# Shield.net
KiCad netlist of a schematic drawn in EAGLE
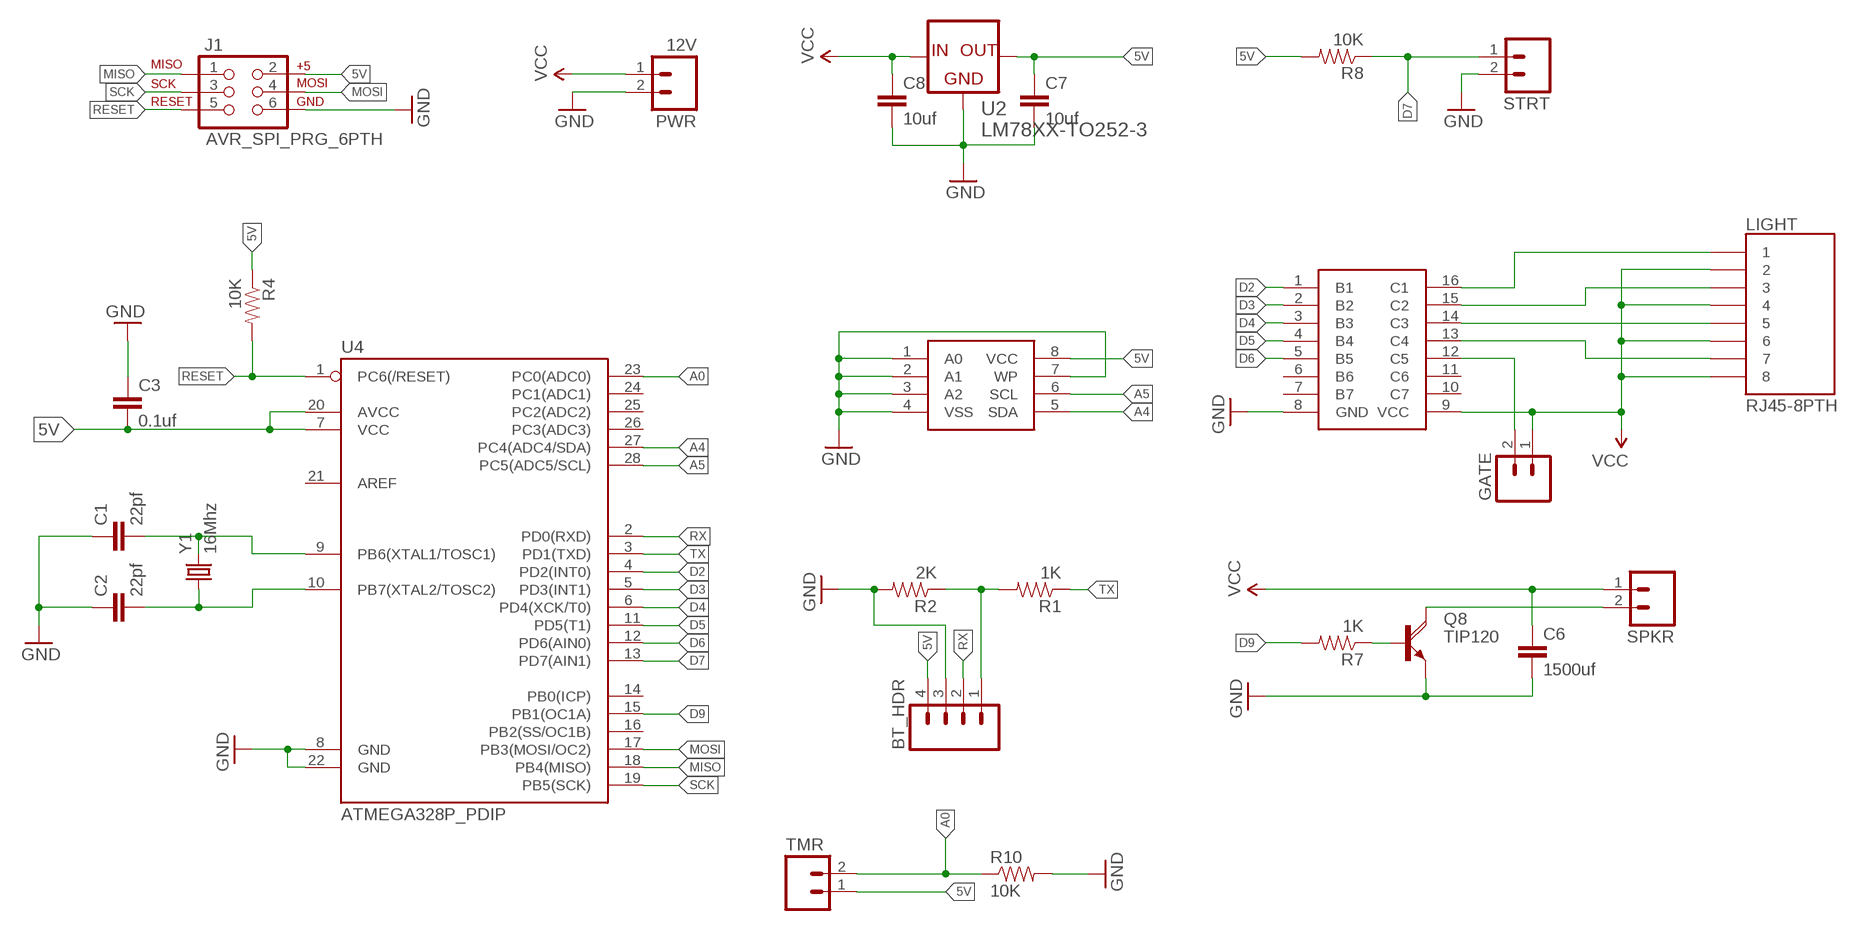
[diagram p0: schematic, sheet 1]

(export (version "E")
  (design (tool "Eeschema 10.0.6"))
  (components
    (comp (ref "BT_HDR")
      (value "M04PTH")
      (footprint "eagle-import:1X04")
      (libsource (lib "eagle-import") (part "M04PTH"))
    )
    (comp (ref "C1")
      (value "22pf")
      (footprint "eagle-import:1206")
      (libsource (lib "eagle-import") (part "CAP1206"))
    )
    (comp (ref "C2")
      (value "22pf")
      (footprint "eagle-import:1206")
      (libsource (lib "eagle-import") (part "CAP1206"))
    )
    (comp (ref "C3")
      (value "0.1uf")
      (footprint "eagle-import:1206")
      (libsource (lib "eagle-import") (part "CAP1206"))
    )
    (comp (ref "C6")
      (value "1500uf")
      (footprint "eagle-import:CAP-PTH-5MM")
      (libsource (lib "eagle-import") (part "CAPPTH1"))
    )
    (comp (ref "C7")
      (value "10uf")
      (footprint "eagle-import:CAP-PTH-SMALL")
      (libsource (lib "eagle-import") (part "CAPPTH"))
    )
    (comp (ref "C8")
      (value "10uf")
      (footprint "eagle-import:CAP-PTH-SMALL")
      (libsource (lib "eagle-import") (part "CAPPTH"))
    )
    (comp (ref "GATE")
      (value "M023.5MM")
      (footprint "eagle-import:SCREWTERMINAL-3.5MM-2")
      (libsource (lib "eagle-import") (part "M023.5MM"))
    )
    (comp (ref "J1")
      (value "AVR_SPI_PRG_6PTH")
      (footprint "eagle-import:2X3")
      (libsource (lib "eagle-import") (part "AVR_SPI_PRG_6PTH"))
    )
    (comp (ref "LIGHT")
      (value "RJ45-8PTH")
      (footprint "eagle-import:RJ45-8")
      (libsource (lib "eagle-import") (part "RJ45-8PTH"))
    )
    (comp (ref "PWR")
      (value "12V")
      (footprint "eagle-import:SCREWTERMINAL-3.5MM-2")
      (libsource (lib "eagle-import") (part "M023.5MM"))
    )
    (comp (ref "Q8")
      (value "TIP120")
      (footprint "eagle-import:TO220V")
      (libsource (lib "eagle-import") (part "TIP120"))
    )
    (comp (ref "R1")
      (value "1K")
      (footprint "eagle-import:1206")
      (libsource (lib "eagle-import") (part "RESISTOR1206"))
    )
    (comp (ref "R2")
      (value "2K")
      (footprint "eagle-import:1206")
      (libsource (lib "eagle-import") (part "RESISTOR1206"))
    )
    (comp (ref "R4")
      (value "10K")
      (footprint "eagle-import:1206")
      (libsource (lib "eagle-import") (part "RESISTOR1206"))
    )
    (comp (ref "R7")
      (value "1K")
      (footprint "eagle-import:1206")
      (libsource (lib "eagle-import") (part "RESISTOR1206"))
    )
    (comp (ref "R8")
      (value "10K")
      (footprint "eagle-import:1206")
      (libsource (lib "eagle-import") (part "RESISTOR1206"))
    )
    (comp (ref "R10")
      (value "10K")
      (footprint "eagle-import:1206")
      (libsource (lib "eagle-import") (part "RESISTOR1206"))
    )
    (comp (ref "SPKR")
      (value "M023.5MM")
      (footprint "eagle-import:SCREWTERMINAL-3.5MM-2")
      (libsource (lib "eagle-import") (part "M023.5MM"))
    )
    (comp (ref "STRT")
      (value "M023.5MM")
      (footprint "eagle-import:SCREWTERMINAL-3.5MM-2")
      (libsource (lib "eagle-import") (part "M023.5MM"))
    )
    (comp (ref "TMR")
      (value "M023.5MM")
      (footprint "eagle-import:SCREWTERMINAL-3.5MM-2")
      (libsource (lib "eagle-import") (part "M023.5MM"))
    )
    (comp (ref "U$1")
      (value "MC1413D")
      (footprint "eagle-import:SO016")
      (libsource (lib "eagle-import") (part "MC1413D"))
    )
    (comp (ref "U$2")
      (value "24AAXXX")
      (footprint "eagle-import:SOIC-8-EIAJ")
      (libsource (lib "eagle-import") (part "24AAXXX"))
    )
    (comp (ref "U2")
      (value "LM78XX-TO252-3")
      (footprint "eagle-import:TO252-3")
      (fields (field (name "MPN") "UA78M33CKVURG3"))
      (libsource (lib "eagle-import") (part "LM78XX-TO252-3"))
    )
    (comp (ref "U4")
      (value "ATMEGA328P_PDIP")
      (footprint "eagle-import:DIL28-3")
      (libsource (lib "eagle-import") (part "ATMEGA328P_PDIP"))
    )
    (comp (ref "Y1")
      (value "16Mhz")
      (footprint "eagle-import:HC49US")
      (libsource (lib "eagle-import") (part "CRYSTALHC49US"))
    )
  )
  (nets
    (net (code "1") (name "5V") (class "Default")
      (node (ref "BT_HDR") (pin "4") (pinfunction "4_4") (pintype "passive"))
      (node (ref "C3") (pin "2") (pinfunction "2_2") (pintype "passive"))
      (node (ref "C7") (pin "1") (pinfunction "1_1") (pintype "passive"))
      (node (ref "J1") (pin "2") (pinfunction "2_2") (pintype "passive"))
      (node (ref "R4") (pin "1") (pinfunction "1_1") (pintype "passive"))
      (node (ref "R8") (pin "2") (pinfunction "2_2") (pintype "passive"))
      (node (ref "TMR") (pin "1") (pinfunction "1_1") (pintype "passive"))
      (node (ref "U$2") (pin "8") (pinfunction "VCC_8") (pintype "bidirectional"))
      (node (ref "U2") (pin "3") (pinfunction "OUT_3") (pintype "output"))
      (node (ref "U4") (pin "20") (pinfunction "AVCC_20") (pintype "bidirectional"))
      (node (ref "U4") (pin "7") (pinfunction "VCC_7") (pintype "bidirectional"))
    )
    (net (code "2") (name "A0") (class "Default")
      (node (ref "R10") (pin "1") (pinfunction "1_1") (pintype "passive"))
      (node (ref "TMR") (pin "2") (pinfunction "2_2") (pintype "passive"))
      (node (ref "U4") (pin "23") (pinfunction "PC0(ADC0)_23") (pintype "bidirectional"))
    )
    (net (code "3") (name "A4") (class "Default")
      (node (ref "U$2") (pin "5") (pinfunction "SDA_5") (pintype "bidirectional"))
      (node (ref "U4") (pin "27") (pinfunction "PC4(ADC4/SDA)_27") (pintype "bidirectional"))
    )
    (net (code "4") (name "A5") (class "Default")
      (node (ref "U$2") (pin "6") (pinfunction "SCL_6") (pintype "bidirectional"))
      (node (ref "U4") (pin "28") (pinfunction "PC5(ADC5/SCL)_28") (pintype "bidirectional"))
    )
    (net (code "5") (name "D2") (class "Default")
      (node (ref "U$1") (pin "1") (pinfunction "B1_1") (pintype "bidirectional"))
      (node (ref "U4") (pin "4") (pinfunction "PD2(INT0)_4") (pintype "bidirectional"))
    )
    (net (code "6") (name "D3") (class "Default")
      (node (ref "U$1") (pin "2") (pinfunction "B2_2") (pintype "bidirectional"))
      (node (ref "U4") (pin "5") (pinfunction "PD3(INT1)_5") (pintype "bidirectional"))
    )
    (net (code "7") (name "D4") (class "Default")
      (node (ref "U$1") (pin "3") (pinfunction "B3_3") (pintype "bidirectional"))
      (node (ref "U4") (pin "6") (pinfunction "PD4(XCK/T0)_6") (pintype "bidirectional"))
    )
    (net (code "8") (name "D5") (class "Default")
      (node (ref "U$1") (pin "4") (pinfunction "B4_4") (pintype "bidirectional"))
      (node (ref "U4") (pin "11") (pinfunction "PD5(T1)_11") (pintype "bidirectional"))
    )
    (net (code "9") (name "D6") (class "Default")
      (node (ref "U$1") (pin "5") (pinfunction "B5_5") (pintype "bidirectional"))
      (node (ref "U4") (pin "12") (pinfunction "PD6(AIN0)_12") (pintype "bidirectional"))
    )
    (net (code "10") (name "D7") (class "Default")
      (node (ref "R8") (pin "1") (pinfunction "1_1") (pintype "passive"))
      (node (ref "STRT") (pin "1") (pinfunction "1_1") (pintype "passive"))
      (node (ref "U4") (pin "13") (pinfunction "PD7(AIN1)_13") (pintype "bidirectional"))
    )
    (net (code "11") (name "D9") (class "Default")
      (node (ref "R7") (pin "2") (pinfunction "2_2") (pintype "passive"))
      (node (ref "U4") (pin "15") (pinfunction "PB1(OC1A)_15") (pintype "bidirectional"))
    )
    (net (code "12") (name "GND") (class "Default")
      (node (ref "BT_HDR") (pin "3") (pinfunction "3_3") (pintype "passive"))
      (node (ref "C1") (pin "1") (pinfunction "1_1") (pintype "passive"))
      (node (ref "C2") (pin "1") (pinfunction "1_1") (pintype "passive"))
      (node (ref "C3") (pin "1") (pinfunction "1_1") (pintype "passive"))
      (node (ref "C6") (pin "2") (pinfunction "2_2") (pintype "passive"))
      (node (ref "C7") (pin "2") (pinfunction "2_2") (pintype "passive"))
      (node (ref "C8") (pin "2") (pinfunction "2_2") (pintype "passive"))
      (node (ref "J1") (pin "6") (pinfunction "6_6") (pintype "passive"))
      (node (ref "PWR") (pin "2") (pinfunction "2_2") (pintype "passive"))
      (node (ref "Q8") (pin "3") (pinfunction "E_3") (pintype "passive"))
      (node (ref "R10") (pin "2") (pinfunction "2_2") (pintype "passive"))
      (node (ref "R2") (pin "2") (pinfunction "2_2") (pintype "passive"))
      (node (ref "STRT") (pin "2") (pinfunction "2_2") (pintype "passive"))
      (node (ref "U$1") (pin "8") (pinfunction "GND_8") (pintype "bidirectional"))
      (node (ref "U$2") (pin "1") (pinfunction "A0_1") (pintype "bidirectional"))
      (node (ref "U$2") (pin "2") (pinfunction "A1_2") (pintype "bidirectional"))
      (node (ref "U$2") (pin "3") (pinfunction "A2_3") (pintype "bidirectional"))
      (node (ref "U$2") (pin "4") (pinfunction "VSS_4") (pintype "bidirectional"))
      (node (ref "U$2") (pin "7") (pinfunction "WP_7") (pintype "bidirectional"))
      (node (ref "U2") (pin "2") (pinfunction "COM_2") (pintype "passive"))
      (node (ref "U4") (pin "22") (pinfunction "GND_22") (pintype "bidirectional"))
      (node (ref "U4") (pin "8") (pinfunction "GND_8") (pintype "bidirectional"))
    )
    (net (code "13") (name "MISO") (class "Default")
      (node (ref "J1") (pin "1") (pinfunction "1_1") (pintype "passive"))
      (node (ref "U4") (pin "18") (pinfunction "PB4(MISO)_18") (pintype "bidirectional"))
    )
    (net (code "14") (name "MOSI") (class "Default")
      (node (ref "J1") (pin "4") (pinfunction "4_4") (pintype "passive"))
      (node (ref "U4") (pin "17") (pinfunction "PB3(MOSI/OC2)_17") (pintype "bidirectional"))
    )
    (net (code "15") (name "Net-(BT_HDR-Pad1)") (class "Default")
      (node (ref "BT_HDR") (pin "1") (pinfunction "1_1") (pintype "passive"))
      (node (ref "R1") (pin "2") (pinfunction "2_2") (pintype "passive"))
      (node (ref "R2") (pin "1") (pinfunction "1_1") (pintype "passive"))
    )
    (net (code "16") (name "Net-(Q8-B)") (class "Default")
      (node (ref "Q8") (pin "1") (pinfunction "B_1") (pintype "passive"))
      (node (ref "R7") (pin "1") (pinfunction "1_1") (pintype "passive"))
    )
    (net (code "17") (name "Net-(Q8-C)") (class "Default")
      (node (ref "Q8") (pin "2") (pinfunction "C_2") (pintype "passive"))
      (node (ref "SPKR") (pin "2") (pinfunction "2_2") (pintype "passive"))
    )
    (net (code "18") (name "Net-(U$1-C1)") (class "Default")
      (node (ref "LIGHT") (pin "1") (pinfunction "1_1") (pintype "bidirectional"))
      (node (ref "U$1") (pin "16") (pinfunction "C1_16") (pintype "bidirectional"))
    )
    (net (code "19") (name "Net-(U$1-C2)") (class "Default")
      (node (ref "LIGHT") (pin "3") (pinfunction "3_3") (pintype "bidirectional"))
      (node (ref "U$1") (pin "15") (pinfunction "C2_15") (pintype "bidirectional"))
    )
    (net (code "20") (name "Net-(U$1-C3)") (class "Default")
      (node (ref "LIGHT") (pin "5") (pinfunction "5_5") (pintype "bidirectional"))
      (node (ref "U$1") (pin "14") (pinfunction "C3_14") (pintype "bidirectional"))
    )
    (net (code "21") (name "Net-(U$1-C4)") (class "Default")
      (node (ref "LIGHT") (pin "7") (pinfunction "7_7") (pintype "bidirectional"))
      (node (ref "U$1") (pin "13") (pinfunction "C4_13") (pintype "bidirectional"))
    )
    (net (code "22") (name "Net-(U$1-C5)") (class "Default")
      (node (ref "GATE") (pin "2") (pinfunction "2_2") (pintype "passive"))
      (node (ref "U$1") (pin "12") (pinfunction "C5_12") (pintype "bidirectional"))
    )
    (net (code "23") (name "Net-(U4-PB6(XTAL1{slash}TOSC1))") (class "Default")
      (node (ref "C1") (pin "2") (pinfunction "2_2") (pintype "passive"))
      (node (ref "U4") (pin "9") (pinfunction "PB6(XTAL1/TOSC1)_9") (pintype "bidirectional"))
      (node (ref "Y1") (pin "2") (pinfunction "2_2") (pintype "passive"))
    )
    (net (code "24") (name "Net-(U4-PB7(XTAL2{slash}TOSC2))") (class "Default")
      (node (ref "C2") (pin "2") (pinfunction "2_2") (pintype "passive"))
      (node (ref "U4") (pin "10") (pinfunction "PB7(XTAL2/TOSC2)_10") (pintype "bidirectional"))
      (node (ref "Y1") (pin "1") (pinfunction "1_1") (pintype "passive"))
    )
    (net (code "25") (name "RESET") (class "Default")
      (node (ref "J1") (pin "5") (pinfunction "5_5") (pintype "passive"))
      (node (ref "R4") (pin "2") (pinfunction "2_2") (pintype "passive"))
      (node (ref "U4") (pin "1") (pinfunction "PC6(/RESET)_1") (pintype "bidirectional"))
    )
    (net (code "26") (name "RX") (class "Default")
      (node (ref "BT_HDR") (pin "2") (pinfunction "2_2") (pintype "passive"))
      (node (ref "U4") (pin "2") (pinfunction "PD0(RXD)_2") (pintype "bidirectional"))
    )
    (net (code "27") (name "SCK") (class "Default")
      (node (ref "J1") (pin "3") (pinfunction "3_3") (pintype "passive"))
      (node (ref "U4") (pin "19") (pinfunction "PB5(SCK)_19") (pintype "bidirectional"))
    )
    (net (code "28") (name "TX") (class "Default")
      (node (ref "R1") (pin "1") (pinfunction "1_1") (pintype "passive"))
      (node (ref "U4") (pin "3") (pinfunction "PD1(TXD)_3") (pintype "bidirectional"))
    )
    (net (code "29") (name "VCC") (class "Default")
      (node (ref "C6") (pin "1") (pinfunction "1_1") (pintype "passive"))
      (node (ref "C8") (pin "1") (pinfunction "1_1") (pintype "passive"))
      (node (ref "GATE") (pin "1") (pinfunction "1_1") (pintype "passive"))
      (node (ref "LIGHT") (pin "2") (pinfunction "2_2") (pintype "bidirectional"))
      (node (ref "LIGHT") (pin "4") (pinfunction "4_4") (pintype "bidirectional"))
      (node (ref "LIGHT") (pin "6") (pinfunction "6_6") (pintype "bidirectional"))
      (node (ref "LIGHT") (pin "8") (pinfunction "8_8") (pintype "bidirectional"))
      (node (ref "PWR") (pin "1") (pinfunction "1_1") (pintype "passive"))
      (node (ref "SPKR") (pin "1") (pinfunction "1_1") (pintype "passive"))
      (node (ref "U$1") (pin "9") (pinfunction "VCC_9") (pintype "bidirectional"))
      (node (ref "U2") (pin "1") (pinfunction "IN_1") (pintype "input"))
    )
    (net (code "30") (name "unconnected-(U$1-B6-Pad6)") (class "Default")
      (node (ref "U$1") (pin "6") (pinfunction "B6_6") (pintype "bidirectional"))
    )
    (net (code "31") (name "unconnected-(U$1-B7-Pad7)") (class "Default")
      (node (ref "U$1") (pin "7") (pinfunction "B7_7") (pintype "bidirectional"))
    )
    (net (code "32") (name "unconnected-(U$1-C6-Pad11)") (class "Default")
      (node (ref "U$1") (pin "11") (pinfunction "C6_11") (pintype "bidirectional"))
    )
    (net (code "33") (name "unconnected-(U$1-C7-Pad10)") (class "Default")
      (node (ref "U$1") (pin "10") (pinfunction "C7_10") (pintype "bidirectional"))
    )
    (net (code "34") (name "unconnected-(U4-AREF-Pad21)") (class "Default")
      (node (ref "U4") (pin "21") (pinfunction "AREF_21") (pintype "bidirectional"))
    )
    (net (code "35") (name "unconnected-(U4-PB0(ICP)-Pad14)") (class "Default")
      (node (ref "U4") (pin "14") (pinfunction "PB0(ICP)_14") (pintype "bidirectional"))
    )
    (net (code "36") (name "unconnected-(U4-PB2(SS{slash}OC1B)-Pad16)") (class "Default")
      (node (ref "U4") (pin "16") (pinfunction "PB2(SS/OC1B)_16") (pintype "bidirectional"))
    )
    (net (code "37") (name "unconnected-(U4-PC1(ADC1)-Pad24)") (class "Default")
      (node (ref "U4") (pin "24") (pinfunction "PC1(ADC1)_24") (pintype "bidirectional"))
    )
    (net (code "38") (name "unconnected-(U4-PC2(ADC2)-Pad25)") (class "Default")
      (node (ref "U4") (pin "25") (pinfunction "PC2(ADC2)_25") (pintype "bidirectional"))
    )
    (net (code "39") (name "unconnected-(U4-PC3(ADC3)-Pad26)") (class "Default")
      (node (ref "U4") (pin "26") (pinfunction "PC3(ADC3)_26") (pintype "bidirectional"))
    )
  )
)
